# AC_BASE-V2_0.net
KiCad netlist of a schematic drawn in Altium Designer
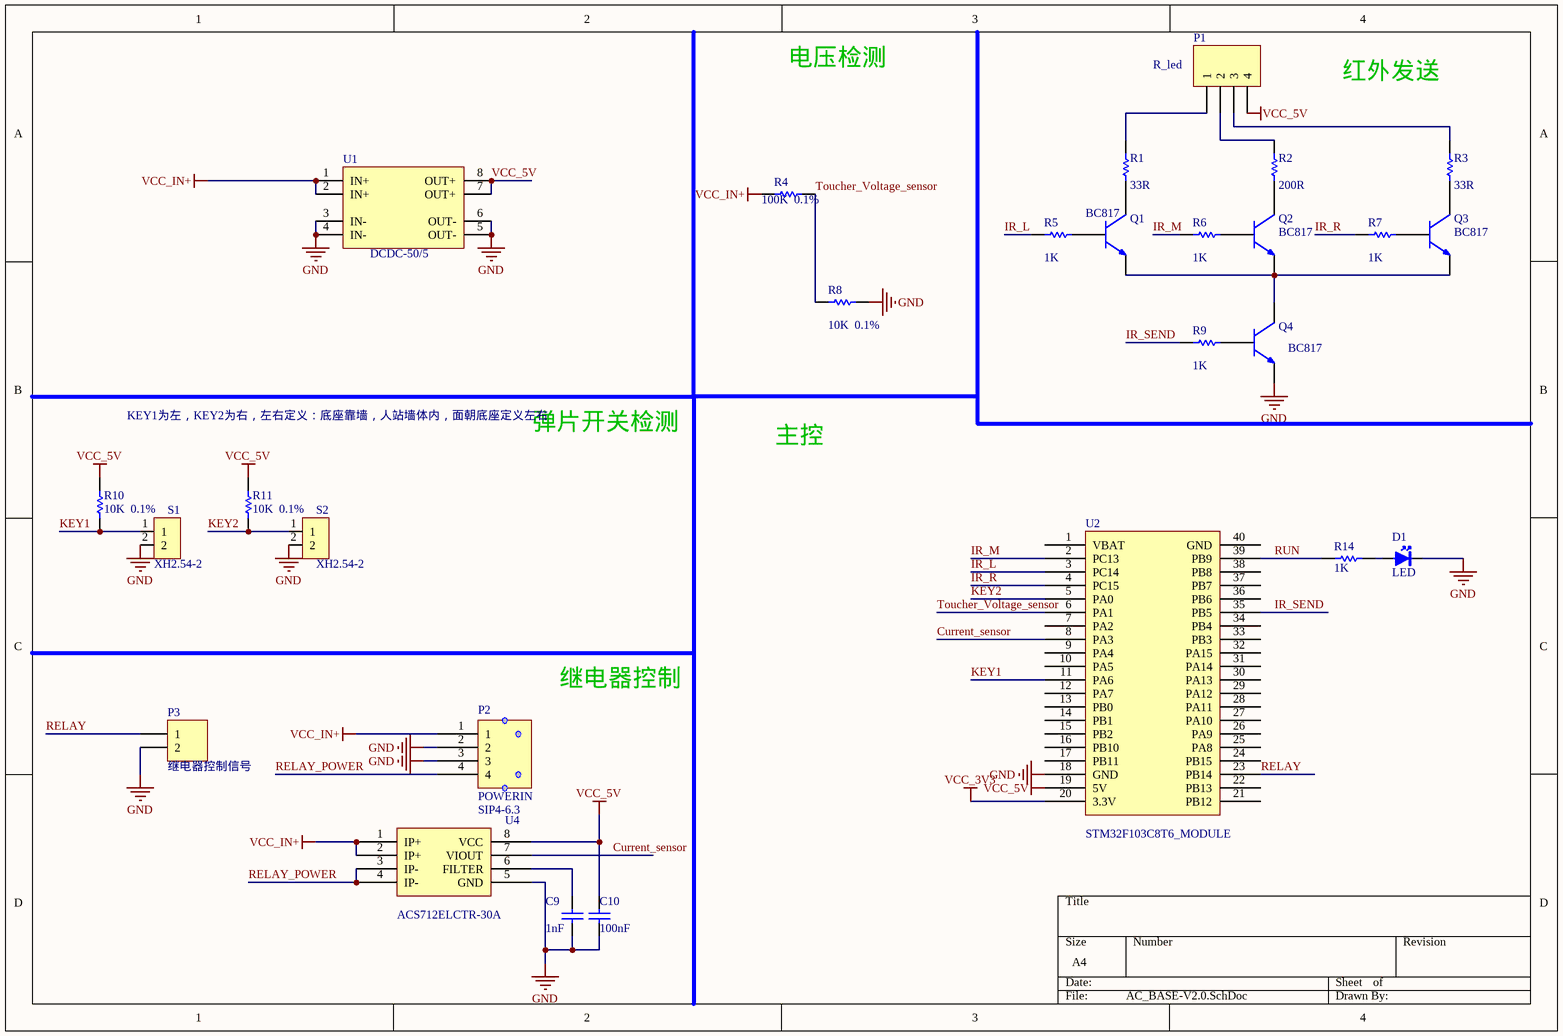
[diagram p0: AC_BASE-V2.0.SchDoc]

(export (version "E")
  (design (tool "Eeschema 10.0.6"))
  (components
    (comp (ref "C9")
      (value "1nF")
      (footprint "boocax_schlib:C0805")
      (description "Capacitor")
      (fields (field (name "Comment") "Cap") (field (name "PUBLISHER") "Altium Limited"))
      (libsource (lib "boocax_schlib") (part "Cap"))
    )
    (comp (ref "C10")
      (value "100nF")
      (footprint "boocax_schlib:C0805")
      (description "Capacitor")
      (fields (field (name "Comment") "Cap") (field (name "PUBLISHER") "Altium Limited"))
      (libsource (lib "boocax_schlib") (part "Cap"))
    )
    (comp (ref "D1")
      (value "LED")
      (footprint "LED-H-R2.54")
      (libsource (lib "boocax_schlib-20171017-1-dkw") (part "LED"))
    )
    (comp (ref "P1")
      (value "R_led")
      (footprint "XH2.54-4P")
      (description "Header, 4-Pin")
      (fields (field (name "PUBLISHER") "Altium Limited"))
      (libsource (lib "Miscellaneous Connectors") (part "Header 4"))
    )
    (comp (ref "P2")
      (value "POWERIN")
      (footprint "boocax_schlib:PORT-SIP4-6.3-WA-LOCK")
      (fields (field (name "ALTIUM_VALUE") "SIP4-6.3"))
      (libsource (lib "boocax_schlib") (part "CONN_4PIN"))
    )
    (comp (ref "P3")
      (value "继电器控制信号")
      (footprint "XH2.54-2P")
      (description "Header, 2-Pin")
      (fields (field (name "PUBLISHER") "Altium Limited"))
      (libsource (lib "Miscellaneous Connectors") (part "Header 2"))
    )
    (comp (ref "Q1")
      (value "BC817")
      (footprint "SOT-23_N")
      (description "NPN 45V 功耗 310mW")
      (libsource (lib "Schlib1") (part "mNPN"))
    )
    (comp (ref "Q2")
      (value "BC817")
      (footprint "SOT-23_N")
      (description "NPN 45V 功耗 310mW")
      (libsource (lib "Schlib1") (part "mNPN"))
    )
    (comp (ref "Q3")
      (value "BC817")
      (footprint "SOT-23_N")
      (description "NPN 45V 功耗 310mW")
      (libsource (lib "Schlib1") (part "mNPN"))
    )
    (comp (ref "Q4")
      (value "BC817")
      (footprint "SOT-23_N")
      (description "NPN 45V 功耗 310mW")
      (libsource (lib "Schlib1") (part "mNPN"))
    )
    (comp (ref "R1")
      (value "33R")
      (footprint "R0805")
      (description "Resistor")
      (fields (field (name "Comment") "Res1") (field (name "PUBLISHER") "Altium Limited"))
      (libsource (lib "boocax_schlib-20171017-1-dkw") (part "Res1"))
    )
    (comp (ref "R2")
      (value "200R")
      (footprint "R0805")
      (description "Resistor")
      (fields (field (name "Comment") "Res1") (field (name "PUBLISHER") "Altium Limited"))
      (libsource (lib "boocax_schlib-20171017-1-dkw") (part "Res1"))
    )
    (comp (ref "R3")
      (value "33R")
      (footprint "R0805")
      (description "Resistor")
      (fields (field (name "Comment") "Res1") (field (name "PUBLISHER") "Altium Limited"))
      (libsource (lib "boocax_schlib-20171017-1-dkw") (part "Res1"))
    )
    (comp (ref "R4")
      (value "100K  0.1%")
      (footprint "R0805")
      (description "Resistor")
      (fields (field (name "Comment") "Res1") (field (name "PUBLISHER") "Altium Limited"))
      (libsource (lib "boocax_schlib-20171017-1-dkw") (part "Res1"))
    )
    (comp (ref "R5")
      (value "1K")
      (footprint "R0805")
      (description "Resistor")
      (fields (field (name "Comment") "Res1") (field (name "PUBLISHER") "Altium Limited"))
      (libsource (lib "boocax_schlib-20171017-1-dkw") (part "Res1"))
    )
    (comp (ref "R6")
      (value "1K")
      (footprint "R0805")
      (description "Resistor")
      (fields (field (name "Comment") "Res1") (field (name "PUBLISHER") "Altium Limited"))
      (libsource (lib "boocax_schlib-20171017-1-dkw") (part "Res1"))
    )
    (comp (ref "R7")
      (value "1K")
      (footprint "R0805")
      (description "Resistor")
      (fields (field (name "Comment") "Res1") (field (name "PUBLISHER") "Altium Limited"))
      (libsource (lib "boocax_schlib-20171017-1-dkw") (part "Res1"))
    )
    (comp (ref "R8")
      (value "10K  0.1%")
      (footprint "R0805")
      (description "Resistor")
      (fields (field (name "Comment") "Res1") (field (name "PUBLISHER") "Altium Limited"))
      (libsource (lib "boocax_schlib-20171017-1-dkw") (part "Res1"))
    )
    (comp (ref "R9")
      (value "1K")
      (footprint "R0805")
      (description "Resistor")
      (fields (field (name "Comment") "Res1") (field (name "PUBLISHER") "Altium Limited"))
      (libsource (lib "boocax_schlib-20171017-1-dkw") (part "Res1"))
    )
    (comp (ref "R10")
      (value "10K  0.1%")
      (footprint "R0805")
      (description "Resistor")
      (fields (field (name "Comment") "Res1") (field (name "PUBLISHER") "Altium Limited"))
      (libsource (lib "boocax_schlib-20171017-1-dkw") (part "Res1"))
    )
    (comp (ref "R11")
      (value "10K  0.1%")
      (footprint "R0805")
      (description "Resistor")
      (fields (field (name "Comment") "Res1") (field (name "PUBLISHER") "Altium Limited"))
      (libsource (lib "boocax_schlib-20171017-1-dkw") (part "Res1"))
    )
    (comp (ref "R14")
      (value "1K")
      (footprint "R0805")
      (description "Resistor")
      (fields (field (name "Comment") "Res1") (field (name "PUBLISHER") "Altium Limited"))
      (libsource (lib "boocax_schlib-20171017-1-dkw") (part "Res1"))
    )
    (comp (ref "S1")
      (value "XH2.54-2")
      (footprint "boocax_schlib:XH2.54-2P")
      (fields (field (name "Comment") "ON"))
      (libsource (lib "boocax_schlib") (part "Conn_1*2"))
    )
    (comp (ref "S2")
      (value "XH2.54-2")
      (footprint "boocax_schlib:XH2.54-2P")
      (fields (field (name "Comment") "ON"))
      (libsource (lib "boocax_schlib") (part "Conn_1*2"))
    )
    (comp (ref "U1")
      (value "DCDC-50/5")
      (footprint "boocax_schlib:DCDC50/5")
      (libsource (lib "boocax_schlib") (part "DCDC-50/5"))
    )
    (comp (ref "U2")
      (value "STM32F103C8T6_MODULE")
      (footprint "STM32F103C8T6_MODE")
      (libsource (lib "boocax_schlib") (part "STM32F103C8T6_MODE"))
    )
    (comp (ref "U4")
      (value "ACS712ELCTR-30A")
      (footprint "ACS712-SOIC8")
      (libsource (lib "boocax_schlib") (part "ACS712"))
    )
  )
  (nets
    (net (code "1") (name "/Current_sensor") (class "Default")
      (node (ref "U2") (pin "8") (pinfunction "PA3_8") (pintype "passive"))
      (node (ref "U4") (pin "7") (pinfunction "VIOUT_7") (pintype "passive"))
    )
    (net (code "2") (name "/IR_L") (class "Default")
      (node (ref "R5") (pin "1") (pinfunction "1_1") (pintype "passive"))
      (node (ref "U2") (pin "3") (pinfunction "PC14_3") (pintype "passive"))
    )
    (net (code "3") (name "/IR_M") (class "Default")
      (node (ref "R6") (pin "1") (pinfunction "1_1") (pintype "passive"))
      (node (ref "U2") (pin "2") (pinfunction "PC13_2") (pintype "passive"))
    )
    (net (code "4") (name "/IR_R") (class "Default")
      (node (ref "R7") (pin "1") (pinfunction "1_1") (pintype "passive"))
      (node (ref "U2") (pin "4") (pinfunction "PC15_4") (pintype "passive"))
    )
    (net (code "5") (name "/IR_SEND") (class "Default")
      (node (ref "R9") (pin "1") (pinfunction "1_1") (pintype "passive"))
      (node (ref "U2") (pin "35") (pinfunction "PB5_35") (pintype "passive"))
    )
    (net (code "6") (name "/KEY1") (class "Default")
      (node (ref "R10") (pin "1") (pinfunction "1_1") (pintype "passive"))
      (node (ref "S1") (pin "1") (pinfunction "1_1") (pintype "passive"))
      (node (ref "U2") (pin "11") (pinfunction "PA6_11") (pintype "passive"))
    )
    (net (code "7") (name "/KEY2") (class "Default")
      (node (ref "R11") (pin "1") (pinfunction "1_1") (pintype "passive"))
      (node (ref "S2") (pin "1") (pinfunction "1_1") (pintype "passive"))
      (node (ref "U2") (pin "5") (pinfunction "PA0_5") (pintype "passive"))
    )
    (net (code "8") (name "/RELAY") (class "Default")
      (node (ref "P3") (pin "1") (pinfunction "1_1") (pintype "passive"))
      (node (ref "U2") (pin "23") (pinfunction "PB14_23") (pintype "passive"))
    )
    (net (code "9") (name "/RELAY_POWER") (class "Default")
      (node (ref "P2") (pin "4") (pinfunction "4_4") (pintype "passive"))
      (node (ref "U4") (pin "3") (pinfunction "IP-_3") (pintype "passive"))
      (node (ref "U4") (pin "4") (pinfunction "IP-_4") (pintype "passive"))
    )
    (net (code "10") (name "/RUN") (class "Default")
      (node (ref "R14") (pin "2") (pinfunction "2_2") (pintype "passive"))
      (node (ref "U2") (pin "39") (pinfunction "PB9_39") (pintype "passive"))
    )
    (net (code "11") (name "/Toucher_Voltage_sensor") (class "Default")
      (node (ref "R4") (pin "2") (pinfunction "2_2") (pintype "passive"))
      (node (ref "R8") (pin "1") (pinfunction "1_1") (pintype "passive"))
      (node (ref "U2") (pin "6") (pinfunction "PA1_6") (pintype "passive"))
    )
    (net (code "12") (name "GND") (class "Default")
      (node (ref "C10") (pin "1") (pinfunction "1_1") (pintype "passive"))
      (node (ref "C9") (pin "1") (pinfunction "1_1") (pintype "passive"))
      (node (ref "D1") (pin "2") (pinfunction "K_2") (pintype "passive"))
      (node (ref "P2") (pin "2") (pinfunction "2_2") (pintype "passive"))
      (node (ref "P2") (pin "3") (pinfunction "3_3") (pintype "passive"))
      (node (ref "P3") (pin "2") (pinfunction "2_2") (pintype "passive"))
      (node (ref "Q4") (pin "2") (pinfunction "E_2") (pintype "passive"))
      (node (ref "R8") (pin "2") (pinfunction "2_2") (pintype "passive"))
      (node (ref "S1") (pin "2") (pinfunction "2_2") (pintype "passive"))
      (node (ref "S2") (pin "2") (pinfunction "2_2") (pintype "passive"))
      (node (ref "U1") (pin "3") (pinfunction "IN-_3") (pintype "passive"))
      (node (ref "U1") (pin "4") (pinfunction "IN-_4") (pintype "passive"))
      (node (ref "U1") (pin "5") (pinfunction "OUT-_5") (pintype "passive"))
      (node (ref "U1") (pin "6") (pinfunction "OUT-_6") (pintype "passive"))
      (node (ref "U2") (pin "18") (pinfunction "GND_18") (pintype "passive"))
      (node (ref "U4") (pin "5") (pinfunction "GND_5") (pintype "passive"))
    )
    (net (code "13") (name "Net-(D1-A)") (class "Default")
      (node (ref "D1") (pin "1") (pinfunction "A_1") (pintype "passive"))
      (node (ref "R14") (pin "1") (pinfunction "1_1") (pintype "passive"))
    )
    (net (code "14") (name "Net-(P1-Pad1)") (class "Default")
      (node (ref "P1") (pin "1") (pinfunction "1_1") (pintype "passive"))
      (node (ref "R1") (pin "2") (pinfunction "2_2") (pintype "passive"))
    )
    (net (code "15") (name "Net-(P1-Pad2)") (class "Default")
      (node (ref "P1") (pin "2") (pinfunction "2_2") (pintype "passive"))
      (node (ref "R2") (pin "2") (pinfunction "2_2") (pintype "passive"))
    )
    (net (code "16") (name "Net-(P1-Pad3)") (class "Default")
      (node (ref "P1") (pin "3") (pinfunction "3_3") (pintype "passive"))
      (node (ref "R3") (pin "2") (pinfunction "2_2") (pintype "passive"))
    )
    (net (code "17") (name "Net-(Q1-B)") (class "Default")
      (node (ref "Q1") (pin "1") (pinfunction "B_1") (pintype "passive"))
      (node (ref "R5") (pin "2") (pinfunction "2_2") (pintype "passive"))
    )
    (net (code "18") (name "Net-(Q1-C)") (class "Default")
      (node (ref "Q1") (pin "3") (pinfunction "C_3") (pintype "passive"))
      (node (ref "R1") (pin "1") (pinfunction "1_1") (pintype "passive"))
    )
    (net (code "19") (name "Net-(Q1-E)") (class "Default")
      (node (ref "Q1") (pin "2") (pinfunction "E_2") (pintype "passive"))
      (node (ref "Q2") (pin "2") (pinfunction "E_2") (pintype "passive"))
      (node (ref "Q3") (pin "2") (pinfunction "E_2") (pintype "passive"))
      (node (ref "Q4") (pin "3") (pinfunction "C_3") (pintype "passive"))
    )
    (net (code "20") (name "Net-(Q2-B)") (class "Default")
      (node (ref "Q2") (pin "1") (pinfunction "B_1") (pintype "passive"))
      (node (ref "R6") (pin "2") (pinfunction "2_2") (pintype "passive"))
    )
    (net (code "21") (name "Net-(Q2-C)") (class "Default")
      (node (ref "Q2") (pin "3") (pinfunction "C_3") (pintype "passive"))
      (node (ref "R2") (pin "1") (pinfunction "1_1") (pintype "passive"))
    )
    (net (code "22") (name "Net-(Q3-B)") (class "Default")
      (node (ref "Q3") (pin "1") (pinfunction "B_1") (pintype "passive"))
      (node (ref "R7") (pin "2") (pinfunction "2_2") (pintype "passive"))
    )
    (net (code "23") (name "Net-(Q3-C)") (class "Default")
      (node (ref "Q3") (pin "3") (pinfunction "C_3") (pintype "passive"))
      (node (ref "R3") (pin "1") (pinfunction "1_1") (pintype "passive"))
    )
    (net (code "24") (name "Net-(Q4-B)") (class "Default")
      (node (ref "Q4") (pin "1") (pinfunction "B_1") (pintype "passive"))
      (node (ref "R9") (pin "2") (pinfunction "2_2") (pintype "passive"))
    )
    (net (code "25") (name "Net-(U4-FILTER)") (class "Default")
      (node (ref "C9") (pin "2") (pinfunction "2_2") (pintype "passive"))
      (node (ref "U4") (pin "6") (pinfunction "FILTER_6") (pintype "passive"))
    )
    (net (code "26") (name "VCC_3V3") (class "Default")
      (node (ref "U2") (pin "20") (pinfunction "3.3V_20") (pintype "passive"))
    )
    (net (code "27") (name "VCC_5V") (class "Default")
      (node (ref "C10") (pin "2") (pinfunction "2_2") (pintype "passive"))
      (node (ref "P1") (pin "4") (pinfunction "4_4") (pintype "passive"))
      (node (ref "R10") (pin "2") (pinfunction "2_2") (pintype "passive"))
      (node (ref "R11") (pin "2") (pinfunction "2_2") (pintype "passive"))
      (node (ref "U1") (pin "7") (pinfunction "OUT+_7") (pintype "passive"))
      (node (ref "U1") (pin "8") (pinfunction "OUT+_8") (pintype "passive"))
      (node (ref "U2") (pin "19") (pinfunction "5V_19") (pintype "passive"))
      (node (ref "U4") (pin "8") (pinfunction "VCC_8") (pintype "passive"))
    )
    (net (code "28") (name "VCC_IN+") (class "Default")
      (node (ref "P2") (pin "1") (pinfunction "1_1") (pintype "passive"))
      (node (ref "R4") (pin "1") (pinfunction "1_1") (pintype "passive"))
      (node (ref "U1") (pin "1") (pinfunction "IN+_1") (pintype "passive"))
      (node (ref "U1") (pin "2") (pinfunction "IN+_2") (pintype "passive"))
      (node (ref "U4") (pin "1") (pinfunction "IP+_1") (pintype "passive"))
      (node (ref "U4") (pin "2") (pinfunction "IP+_2") (pintype "passive"))
    )
    (net (code "29") (name "unconnected-(U2-GND-Pad40)") (class "Default")
      (node (ref "U2") (pin "40") (pinfunction "GND_40") (pintype "passive"))
    )
    (net (code "30") (name "unconnected-(U2-PA2-Pad7)") (class "Default")
      (node (ref "U2") (pin "7") (pinfunction "PA2_7") (pintype "passive"))
    )
    (net (code "31") (name "unconnected-(U2-PA4-Pad9)") (class "Default")
      (node (ref "U2") (pin "9") (pinfunction "PA4_9") (pintype "passive"))
    )
    (net (code "32") (name "unconnected-(U2-PA5-Pad10)") (class "Default")
      (node (ref "U2") (pin "10") (pinfunction "PA5_10") (pintype "passive"))
    )
    (net (code "33") (name "unconnected-(U2-PA7-Pad12)") (class "Default")
      (node (ref "U2") (pin "12") (pinfunction "PA7_12") (pintype "passive"))
    )
    (net (code "34") (name "unconnected-(U2-PA8-Pad25)") (class "Default")
      (node (ref "U2") (pin "25") (pinfunction "PA8_25") (pintype "passive"))
    )
    (net (code "35") (name "unconnected-(U2-PA9-Pad26)") (class "Default")
      (node (ref "U2") (pin "26") (pinfunction "PA9_26") (pintype "passive"))
    )
    (net (code "36") (name "unconnected-(U2-PA10-Pad27)") (class "Default")
      (node (ref "U2") (pin "27") (pinfunction "PA10_27") (pintype "passive"))
    )
    (net (code "37") (name "unconnected-(U2-PA11-Pad28)") (class "Default")
      (node (ref "U2") (pin "28") (pinfunction "PA11_28") (pintype "passive"))
    )
    (net (code "38") (name "unconnected-(U2-PA12-Pad29)") (class "Default")
      (node (ref "U2") (pin "29") (pinfunction "PA12_29") (pintype "passive"))
    )
    (net (code "39") (name "unconnected-(U2-PA13-Pad30)") (class "Default")
      (node (ref "U2") (pin "30") (pinfunction "PA13_30") (pintype "passive"))
    )
    (net (code "40") (name "unconnected-(U2-PA14-Pad31)") (class "Default")
      (node (ref "U2") (pin "31") (pinfunction "PA14_31") (pintype "passive"))
    )
    (net (code "41") (name "unconnected-(U2-PA15-Pad32)") (class "Default")
      (node (ref "U2") (pin "32") (pinfunction "PA15_32") (pintype "passive"))
    )
    (net (code "42") (name "unconnected-(U2-PB0-Pad13)") (class "Default")
      (node (ref "U2") (pin "13") (pinfunction "PB0_13") (pintype "passive"))
    )
    (net (code "43") (name "unconnected-(U2-PB1-Pad14)") (class "Default")
      (node (ref "U2") (pin "14") (pinfunction "PB1_14") (pintype "passive"))
    )
    (net (code "44") (name "unconnected-(U2-PB2-Pad15)") (class "Default")
      (node (ref "U2") (pin "15") (pinfunction "PB2_15") (pintype "passive"))
    )
    (net (code "45") (name "unconnected-(U2-PB3-Pad33)") (class "Default")
      (node (ref "U2") (pin "33") (pinfunction "PB3_33") (pintype "passive"))
    )
    (net (code "46") (name "unconnected-(U2-PB4-Pad34)") (class "Default")
      (node (ref "U2") (pin "34") (pinfunction "PB4_34") (pintype "passive"))
    )
    (net (code "47") (name "unconnected-(U2-PB6-Pad36)") (class "Default")
      (node (ref "U2") (pin "36") (pinfunction "PB6_36") (pintype "passive"))
    )
    (net (code "48") (name "unconnected-(U2-PB7-Pad37)") (class "Default")
      (node (ref "U2") (pin "37") (pinfunction "PB7_37") (pintype "passive"))
    )
    (net (code "49") (name "unconnected-(U2-PB8-Pad38)") (class "Default")
      (node (ref "U2") (pin "38") (pinfunction "PB8_38") (pintype "passive"))
    )
    (net (code "50") (name "unconnected-(U2-PB10-Pad16)") (class "Default")
      (node (ref "U2") (pin "16") (pinfunction "PB10_16") (pintype "passive"))
    )
    (net (code "51") (name "unconnected-(U2-PB11-Pad17)") (class "Default")
      (node (ref "U2") (pin "17") (pinfunction "PB11_17") (pintype "passive"))
    )
    (net (code "52") (name "unconnected-(U2-PB12-Pad21)") (class "Default")
      (node (ref "U2") (pin "21") (pinfunction "PB12_21") (pintype "passive"))
    )
    (net (code "53") (name "unconnected-(U2-PB13-Pad22)") (class "Default")
      (node (ref "U2") (pin "22") (pinfunction "PB13_22") (pintype "passive"))
    )
    (net (code "54") (name "unconnected-(U2-PB15-Pad24)") (class "Default")
      (node (ref "U2") (pin "24") (pinfunction "PB15_24") (pintype "passive"))
    )
    (net (code "55") (name "unconnected-(U2-VBAT-Pad1)") (class "Default")
      (node (ref "U2") (pin "1") (pinfunction "VBAT_1") (pintype "passive"))
    )
  )
)
